# attinier85-motherboard-smd-mk-2_0.net
KiCad netlist of a schematic drawn in EAGLE
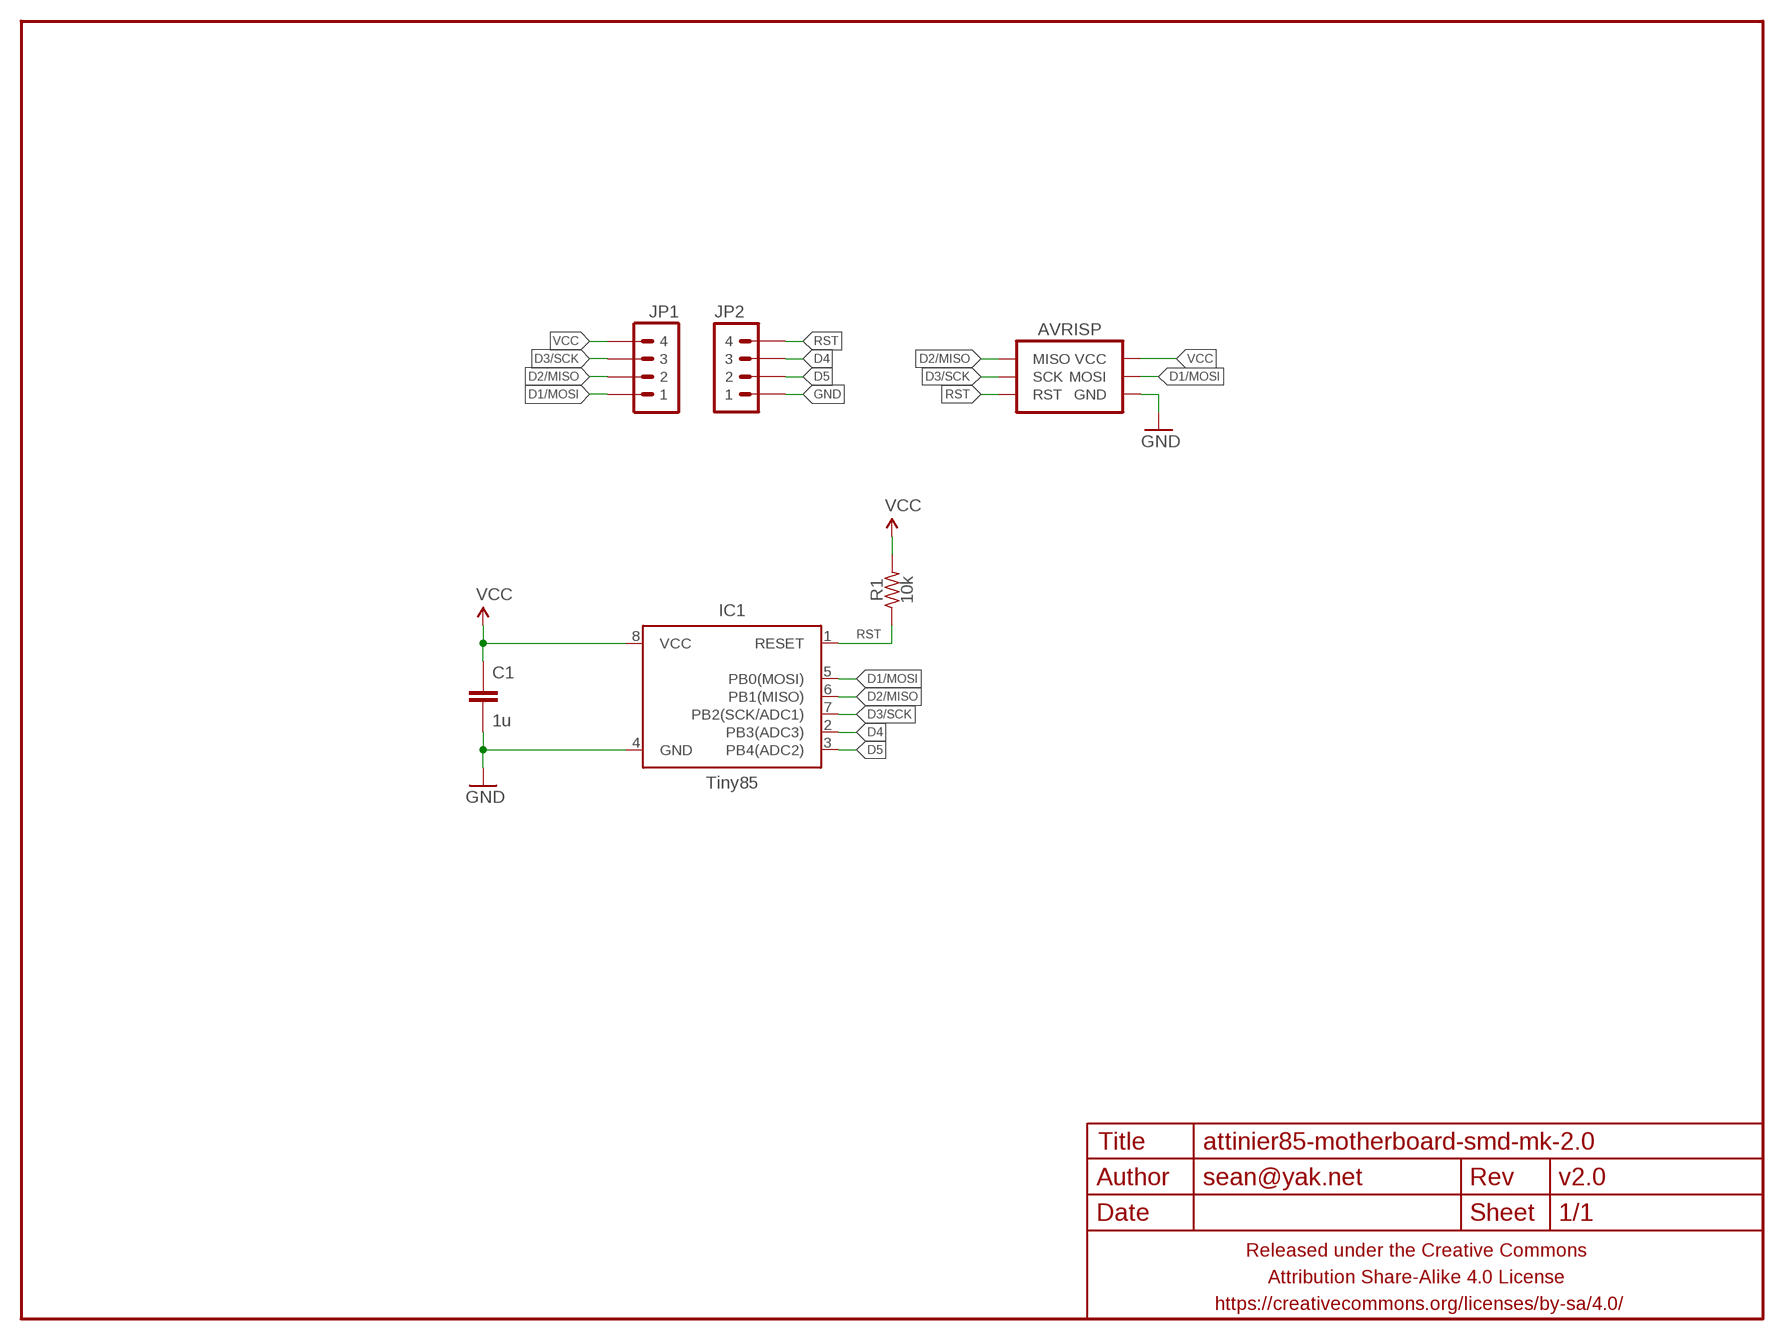
[diagram p0: schematic, sheet 1]

(export (version "E")
  (design (tool "Eeschema 10.0.6"))
  (components
    (comp (ref "AVRISP")
      (value "AVR_SPI_PRG_6SMD_TEST_POINTS")
      (footprint "eagle-import:2X3_SMD_TEST_POINTS")
      (libsource (lib "eagle-import") (part "AVR_SPI_PRG_6SMD_TEST_POINTS"))
    )
    (comp (ref "C1")
      (value "1u")
      (footprint "eagle-import:C0603-TIGHTER")
      (libsource (lib "eagle-import") (part "CAPACITOR-CERAMICC0603-TIGHTER"))
    )
    (comp (ref "FRAME1")
      (value "FRAME-LETTERNO_PACKAGE")
      (footprint "eagle-import:DUMMY")
      (fields (field (name "DESIGNER") "sean@yak.net") (field (name "VERSION") "v2.0"))
      (libsource (lib "eagle-import") (part "FRAME-LETTERNO_PACKAGE"))
    )
    (comp (ref "IC1")
      (value "Tiny85")
      (footprint "eagle-import:SO08-EIAJ")
      (libsource (lib "eagle-import") (part "ATTINY45TINY85-20-SOICW"))
    )
    (comp (ref "JP1")
      (value "M04PTH")
      (footprint "eagle-import:1X04-PTH-VERT")
      (libsource (lib "eagle-import") (part "M04PTH"))
    )
    (comp (ref "JP2")
      (value "M04PTH")
      (footprint "eagle-import:1X04-PTH-VERT")
      (libsource (lib "eagle-import") (part "M04PTH"))
    )
    (comp (ref "R1")
      (value "10k")
      (footprint "eagle-import:R0603-TIGHTER")
      (libsource (lib "eagle-import") (part "RESISTORR0603-TIGHTER"))
    )
  )
  (nets
    (net (code "1") (name "D1{slash}MOSI") (class "Default")
      (node (ref "AVRISP") (pin "4") (pinfunction "MOSI_4") (pintype "passive"))
      (node (ref "IC1") (pin "5") (pinfunction "PB0(MOSI)_5") (pintype "bidirectional"))
      (node (ref "JP1") (pin "1") (pinfunction "1_1") (pintype "passive"))
    )
    (net (code "2") (name "D2{slash}MISO") (class "Default")
      (node (ref "AVRISP") (pin "1") (pinfunction "MISO_1") (pintype "passive"))
      (node (ref "IC1") (pin "6") (pinfunction "PB1(MISO)_6") (pintype "bidirectional"))
      (node (ref "JP1") (pin "2") (pinfunction "2_2") (pintype "passive"))
    )
    (net (code "3") (name "D3{slash}SCK") (class "Default")
      (node (ref "AVRISP") (pin "3") (pinfunction "SCK_3") (pintype "passive"))
      (node (ref "IC1") (pin "7") (pinfunction "PB2(SCK/ADC1)_7") (pintype "bidirectional"))
      (node (ref "JP1") (pin "3") (pinfunction "3_3") (pintype "passive"))
    )
    (net (code "4") (name "D4") (class "Default")
      (node (ref "IC1") (pin "2") (pinfunction "PB3(ADC3)_2") (pintype "bidirectional"))
      (node (ref "JP2") (pin "3") (pinfunction "3_3") (pintype "passive"))
    )
    (net (code "5") (name "D5") (class "Default")
      (node (ref "IC1") (pin "3") (pinfunction "PB4(ADC2)_3") (pintype "bidirectional"))
      (node (ref "JP2") (pin "2") (pinfunction "2_2") (pintype "passive"))
    )
    (net (code "6") (name "GND") (class "Default")
      (node (ref "AVRISP") (pin "6") (pinfunction "GND_6") (pintype "passive"))
      (node (ref "C1") (pin "2") (pinfunction "2_2") (pintype "passive"))
      (node (ref "IC1") (pin "4") (pinfunction "GND_4") (pintype "bidirectional"))
      (node (ref "JP2") (pin "1") (pinfunction "1_1") (pintype "passive"))
    )
    (net (code "7") (name "RST") (class "Default")
      (node (ref "AVRISP") (pin "5") (pinfunction "RST_5") (pintype "passive"))
      (node (ref "IC1") (pin "1") (pinfunction "RESET_1") (pintype "bidirectional"))
      (node (ref "JP2") (pin "4") (pinfunction "4_4") (pintype "passive"))
      (node (ref "R1") (pin "1") (pinfunction "1_1") (pintype "passive"))
    )
    (net (code "8") (name "VCC") (class "Default")
      (node (ref "AVRISP") (pin "2") (pinfunction "VCC_2") (pintype "passive"))
      (node (ref "C1") (pin "1") (pinfunction "1_1") (pintype "passive"))
      (node (ref "IC1") (pin "8") (pinfunction "VCC_8") (pintype "bidirectional"))
      (node (ref "JP1") (pin "4") (pinfunction "4_4") (pintype "passive"))
      (node (ref "R1") (pin "2") (pinfunction "2_2") (pintype "passive"))
    )
  )
)
